# hp45BR.net
KiCad netlist of a schematic drawn in Altium Designer
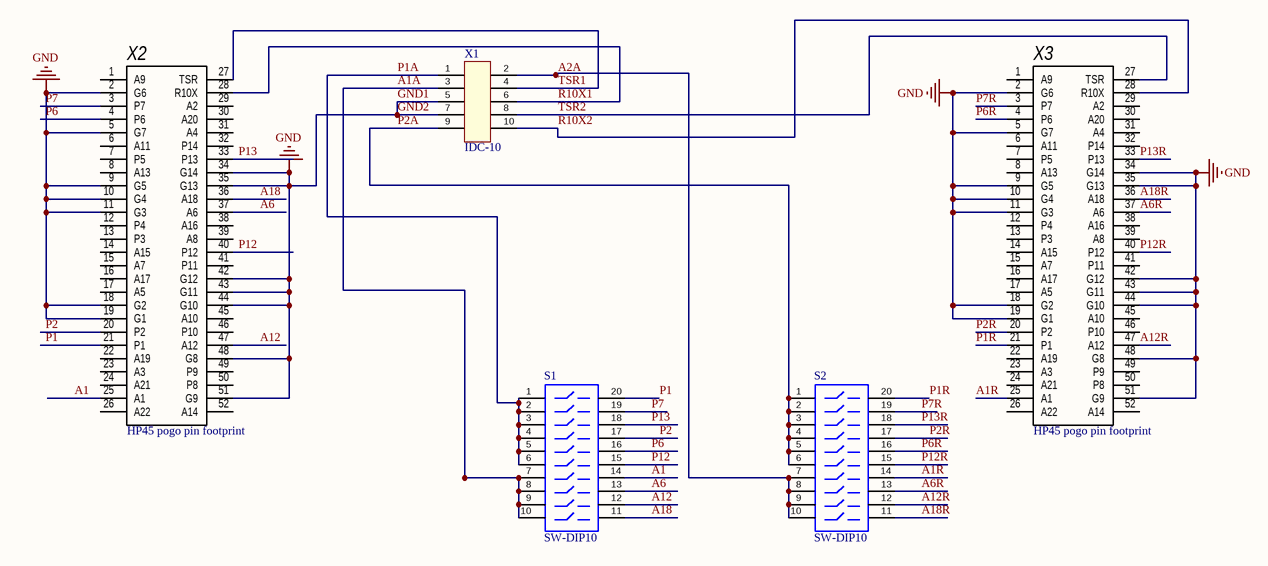
[diagram p0: hp45BR.SchDoc]

(export (version "E")
  (design (tool "Eeschema 10.0.6"))
  (components
    (comp (ref "S1")
      (value "SW-DIP10")
      (footprint "DIP-20-KEY")
      (description "4009 Series DIP Switch, Raised actuator")
      (fields (field (name "PUBLISHER") "Altium Limited"))
      (libsource (lib "RCU") (part "SW-DIP10"))
    )
    (comp (ref "S2")
      (value "SW-DIP10")
      (footprint "DIP-20-KEY")
      (description "4009 Series DIP Switch, Raised actuator")
      (fields (field (name "PUBLISHER") "Altium Limited"))
      (libsource (lib "RCU") (part "SW-DIP10"))
    )
    (comp (ref "X1")
      (value "IDC-10")
      (footprint "IDC-10")
      (description "разъем 4130")
      (libsource (lib "RCU") (part "IDC-10"))
    )
    (comp (ref "X2")
      (value "HP45 pogo pin footprint")
      (footprint "HP45")
      (libsource (lib "HP45") (part "HP45"))
    )
    (comp (ref "X3")
      (value "HP45 pogo pin footprint")
      (footprint "HP45")
      (libsource (lib "HP45") (part "HP45"))
    )
  )
  (nets
    (net (code "1") (name "/A1") (class "Default")
      (node (ref "S1") (pin "14") (pinfunction "14_14") (pintype "passive"))
      (node (ref "X2") (pin "25") (pinfunction "A1_25") (pintype "passive"))
    )
    (net (code "2") (name "/A1A") (class "Default")
      (node (ref "S1") (pin "10") (pinfunction "10_10") (pintype "passive"))
      (node (ref "S1") (pin "7") (pinfunction "7_7") (pintype "passive"))
      (node (ref "S1") (pin "8") (pinfunction "8_8") (pintype "passive"))
      (node (ref "S1") (pin "9") (pinfunction "9_9") (pintype "passive"))
      (node (ref "X1") (pin "3") (pinfunction "3_3") (pintype "passive"))
    )
    (net (code "3") (name "/A1R") (class "Default")
      (node (ref "S2") (pin "14") (pinfunction "14_14") (pintype "passive"))
      (node (ref "X3") (pin "25") (pinfunction "A1_25") (pintype "passive"))
    )
    (net (code "4") (name "/A2A") (class "Default")
      (node (ref "S2") (pin "10") (pinfunction "10_10") (pintype "passive"))
      (node (ref "S2") (pin "7") (pinfunction "7_7") (pintype "passive"))
      (node (ref "S2") (pin "8") (pinfunction "8_8") (pintype "passive"))
      (node (ref "S2") (pin "9") (pinfunction "9_9") (pintype "passive"))
      (node (ref "X1") (pin "2") (pinfunction "2_2") (pintype "passive"))
    )
    (net (code "5") (name "/A6") (class "Default")
      (node (ref "S1") (pin "13") (pinfunction "13_13") (pintype "passive"))
      (node (ref "X2") (pin "37") (pinfunction "A6_37") (pintype "passive"))
    )
    (net (code "6") (name "/A6R") (class "Default")
      (node (ref "S2") (pin "13") (pinfunction "13_13") (pintype "passive"))
      (node (ref "X3") (pin "37") (pinfunction "A6_37") (pintype "passive"))
    )
    (net (code "7") (name "/A12") (class "Default")
      (node (ref "S1") (pin "12") (pinfunction "12_12") (pintype "passive"))
      (node (ref "X2") (pin "47") (pinfunction "A12_47") (pintype "passive"))
    )
    (net (code "8") (name "/A12R") (class "Default")
      (node (ref "S2") (pin "12") (pinfunction "12_12") (pintype "passive"))
      (node (ref "X3") (pin "47") (pinfunction "A12_47") (pintype "passive"))
    )
    (net (code "9") (name "/A18") (class "Default")
      (node (ref "S1") (pin "11") (pinfunction "11_11") (pintype "passive"))
      (node (ref "X2") (pin "36") (pinfunction "A18_36") (pintype "passive"))
    )
    (net (code "10") (name "/A18R") (class "Default")
      (node (ref "S2") (pin "11") (pinfunction "11_11") (pintype "passive"))
      (node (ref "X3") (pin "36") (pinfunction "A18_36") (pintype "passive"))
    )
    (net (code "11") (name "/P1") (class "Default")
      (node (ref "S1") (pin "20") (pinfunction "20_20") (pintype "passive"))
      (node (ref "X2") (pin "21") (pinfunction "P1_21") (pintype "passive"))
    )
    (net (code "12") (name "/P1A") (class "Default")
      (node (ref "S1") (pin "1") (pinfunction "1_1") (pintype "passive"))
      (node (ref "S1") (pin "2") (pinfunction "2_2") (pintype "passive"))
      (node (ref "S1") (pin "3") (pinfunction "3_3") (pintype "passive"))
      (node (ref "S1") (pin "4") (pinfunction "4_4") (pintype "passive"))
      (node (ref "S1") (pin "5") (pinfunction "5_5") (pintype "passive"))
      (node (ref "S1") (pin "6") (pinfunction "6_6") (pintype "passive"))
      (node (ref "X1") (pin "1") (pinfunction "1_1") (pintype "passive"))
    )
    (net (code "13") (name "/P1R") (class "Default")
      (node (ref "S2") (pin "20") (pinfunction "20_20") (pintype "passive"))
      (node (ref "X3") (pin "21") (pinfunction "P1_21") (pintype "passive"))
    )
    (net (code "14") (name "/P2") (class "Default")
      (node (ref "S1") (pin "17") (pinfunction "17_17") (pintype "passive"))
      (node (ref "X2") (pin "20") (pinfunction "P2_20") (pintype "passive"))
    )
    (net (code "15") (name "/P2A") (class "Default")
      (node (ref "S2") (pin "1") (pinfunction "1_1") (pintype "passive"))
      (node (ref "S2") (pin "2") (pinfunction "2_2") (pintype "passive"))
      (node (ref "S2") (pin "3") (pinfunction "3_3") (pintype "passive"))
      (node (ref "S2") (pin "4") (pinfunction "4_4") (pintype "passive"))
      (node (ref "S2") (pin "5") (pinfunction "5_5") (pintype "passive"))
      (node (ref "S2") (pin "6") (pinfunction "6_6") (pintype "passive"))
      (node (ref "X1") (pin "9") (pinfunction "9_9") (pintype "passive"))
    )
    (net (code "16") (name "/P2R") (class "Default")
      (node (ref "S2") (pin "17") (pinfunction "17_17") (pintype "passive"))
      (node (ref "X3") (pin "20") (pinfunction "P2_20") (pintype "passive"))
    )
    (net (code "17") (name "/P6") (class "Default")
      (node (ref "S1") (pin "16") (pinfunction "16_16") (pintype "passive"))
      (node (ref "X2") (pin "4") (pinfunction "P6_4") (pintype "passive"))
    )
    (net (code "18") (name "/P6R") (class "Default")
      (node (ref "S2") (pin "16") (pinfunction "16_16") (pintype "passive"))
      (node (ref "X3") (pin "4") (pinfunction "P6_4") (pintype "passive"))
    )
    (net (code "19") (name "/P7") (class "Default")
      (node (ref "S1") (pin "19") (pinfunction "19_19") (pintype "passive"))
      (node (ref "X2") (pin "3") (pinfunction "P7_3") (pintype "passive"))
    )
    (net (code "20") (name "/P7R") (class "Default")
      (node (ref "S2") (pin "19") (pinfunction "19_19") (pintype "passive"))
      (node (ref "X3") (pin "3") (pinfunction "P7_3") (pintype "passive"))
    )
    (net (code "21") (name "/P12") (class "Default")
      (node (ref "S1") (pin "15") (pinfunction "15_15") (pintype "passive"))
      (node (ref "X2") (pin "40") (pinfunction "P12_40") (pintype "passive"))
    )
    (net (code "22") (name "/P12R") (class "Default")
      (node (ref "S2") (pin "15") (pinfunction "15_15") (pintype "passive"))
      (node (ref "X3") (pin "40") (pinfunction "P12_40") (pintype "passive"))
    )
    (net (code "23") (name "/P13") (class "Default")
      (node (ref "S1") (pin "18") (pinfunction "18_18") (pintype "passive"))
      (node (ref "X2") (pin "33") (pinfunction "P13_33") (pintype "passive"))
    )
    (net (code "24") (name "/P13R") (class "Default")
      (node (ref "S2") (pin "18") (pinfunction "18_18") (pintype "passive"))
      (node (ref "X3") (pin "33") (pinfunction "P13_33") (pintype "passive"))
    )
    (net (code "25") (name "/R10X1") (class "Default")
      (node (ref "X1") (pin "6") (pinfunction "6_6") (pintype "passive"))
      (node (ref "X2") (pin "28") (pinfunction "R10X_28") (pintype "passive"))
    )
    (net (code "26") (name "/R10X2") (class "Default")
      (node (ref "X1") (pin "10") (pinfunction "10_10") (pintype "passive"))
      (node (ref "X3") (pin "28") (pinfunction "R10X_28") (pintype "passive"))
    )
    (net (code "27") (name "/TSR1") (class "Default")
      (node (ref "X1") (pin "4") (pinfunction "4_4") (pintype "passive"))
      (node (ref "X2") (pin "27") (pinfunction "TSR_27") (pintype "passive"))
    )
    (net (code "28") (name "/TSR2") (class "Default")
      (node (ref "X1") (pin "8") (pinfunction "8_8") (pintype "passive"))
      (node (ref "X3") (pin "27") (pinfunction "TSR_27") (pintype "passive"))
    )
    (net (code "29") (name "GND") (class "Default")
      (node (ref "X1") (pin "5") (pinfunction "5_5") (pintype "passive"))
      (node (ref "X1") (pin "7") (pinfunction "7_7") (pintype "passive"))
      (node (ref "X2") (pin "10") (pinfunction "G4_10") (pintype "passive"))
      (node (ref "X2") (pin "11") (pinfunction "G3_11") (pintype "passive"))
      (node (ref "X2") (pin "18") (pinfunction "G2_18") (pintype "passive"))
      (node (ref "X2") (pin "19") (pinfunction "G1_19") (pintype "passive"))
      (node (ref "X2") (pin "2") (pinfunction "G6_2") (pintype "passive"))
      (node (ref "X2") (pin "34") (pinfunction "G14_34") (pintype "passive"))
      (node (ref "X2") (pin "35") (pinfunction "G13_35") (pintype "passive"))
      (node (ref "X2") (pin "42") (pinfunction "G12_42") (pintype "passive"))
      (node (ref "X2") (pin "43") (pinfunction "G11_43") (pintype "passive"))
      (node (ref "X2") (pin "44") (pinfunction "G10_44") (pintype "passive"))
      (node (ref "X2") (pin "48") (pinfunction "G8_48") (pintype "passive"))
      (node (ref "X2") (pin "5") (pinfunction "G7_5") (pintype "passive"))
      (node (ref "X2") (pin "51") (pinfunction "G9_51") (pintype "passive"))
      (node (ref "X2") (pin "9") (pinfunction "G5_9") (pintype "passive"))
      (node (ref "X3") (pin "10") (pinfunction "G4_10") (pintype "passive"))
      (node (ref "X3") (pin "11") (pinfunction "G3_11") (pintype "passive"))
      (node (ref "X3") (pin "18") (pinfunction "G2_18") (pintype "passive"))
      (node (ref "X3") (pin "19") (pinfunction "G1_19") (pintype "passive"))
      (node (ref "X3") (pin "2") (pinfunction "G6_2") (pintype "passive"))
      (node (ref "X3") (pin "34") (pinfunction "G14_34") (pintype "passive"))
      (node (ref "X3") (pin "35") (pinfunction "G13_35") (pintype "passive"))
      (node (ref "X3") (pin "42") (pinfunction "G12_42") (pintype "passive"))
      (node (ref "X3") (pin "43") (pinfunction "G11_43") (pintype "passive"))
      (node (ref "X3") (pin "44") (pinfunction "G10_44") (pintype "passive"))
      (node (ref "X3") (pin "48") (pinfunction "G8_48") (pintype "passive"))
      (node (ref "X3") (pin "5") (pinfunction "G7_5") (pintype "passive"))
      (node (ref "X3") (pin "51") (pinfunction "G9_51") (pintype "passive"))
      (node (ref "X3") (pin "9") (pinfunction "G5_9") (pintype "passive"))
    )
    (net (code "30") (name "unconnected-(X2-A2-Pad29)") (class "Default")
      (node (ref "X2") (pin "29") (pinfunction "A2_29") (pintype "passive"))
    )
    (net (code "31") (name "unconnected-(X2-A3-Pad23)") (class "Default")
      (node (ref "X2") (pin "23") (pinfunction "A3_23") (pintype "passive"))
    )
    (net (code "32") (name "unconnected-(X2-A4-Pad31)") (class "Default")
      (node (ref "X2") (pin "31") (pinfunction "A4_31") (pintype "passive"))
    )
    (net (code "33") (name "unconnected-(X2-A5-Pad17)") (class "Default")
      (node (ref "X2") (pin "17") (pinfunction "A5_17") (pintype "passive"))
    )
    (net (code "34") (name "unconnected-(X2-A7-Pad15)") (class "Default")
      (node (ref "X2") (pin "15") (pinfunction "A7_15") (pintype "passive"))
    )
    (net (code "35") (name "unconnected-(X2-A8-Pad39)") (class "Default")
      (node (ref "X2") (pin "39") (pinfunction "A8_39") (pintype "passive"))
    )
    (net (code "36") (name "unconnected-(X2-A9-Pad1)") (class "Default")
      (node (ref "X2") (pin "1") (pinfunction "A9_1") (pintype "passive"))
    )
    (net (code "37") (name "unconnected-(X2-A10-Pad45)") (class "Default")
      (node (ref "X2") (pin "45") (pinfunction "A10_45") (pintype "passive"))
    )
    (net (code "38") (name "unconnected-(X2-A11-Pad6)") (class "Default")
      (node (ref "X2") (pin "6") (pinfunction "A11_6") (pintype "passive"))
    )
    (net (code "39") (name "unconnected-(X2-A13-Pad8)") (class "Default")
      (node (ref "X2") (pin "8") (pinfunction "A13_8") (pintype "passive"))
    )
    (net (code "40") (name "unconnected-(X2-A14-Pad52)") (class "Default")
      (node (ref "X2") (pin "52") (pinfunction "A14_52") (pintype "passive"))
    )
    (net (code "41") (name "unconnected-(X2-A15-Pad14)") (class "Default")
      (node (ref "X2") (pin "14") (pinfunction "A15_14") (pintype "passive"))
    )
    (net (code "42") (name "unconnected-(X2-A16-Pad38)") (class "Default")
      (node (ref "X2") (pin "38") (pinfunction "A16_38") (pintype "passive"))
    )
    (net (code "43") (name "unconnected-(X2-A17-Pad16)") (class "Default")
      (node (ref "X2") (pin "16") (pinfunction "A17_16") (pintype "passive"))
    )
    (net (code "44") (name "unconnected-(X2-A19-Pad22)") (class "Default")
      (node (ref "X2") (pin "22") (pinfunction "A19_22") (pintype "passive"))
    )
    (net (code "45") (name "unconnected-(X2-A20-Pad30)") (class "Default")
      (node (ref "X2") (pin "30") (pinfunction "A20_30") (pintype "passive"))
    )
    (net (code "46") (name "unconnected-(X2-A21-Pad24)") (class "Default")
      (node (ref "X2") (pin "24") (pinfunction "A21_24") (pintype "passive"))
    )
    (net (code "47") (name "unconnected-(X2-A22-Pad26)") (class "Default")
      (node (ref "X2") (pin "26") (pinfunction "A22_26") (pintype "passive"))
    )
    (net (code "48") (name "unconnected-(X2-P3-Pad13)") (class "Default")
      (node (ref "X2") (pin "13") (pinfunction "P3_13") (pintype "passive"))
    )
    (net (code "49") (name "unconnected-(X2-P4-Pad12)") (class "Default")
      (node (ref "X2") (pin "12") (pinfunction "P4_12") (pintype "passive"))
    )
    (net (code "50") (name "unconnected-(X2-P5-Pad7)") (class "Default")
      (node (ref "X2") (pin "7") (pinfunction "P5_7") (pintype "passive"))
    )
    (net (code "51") (name "unconnected-(X2-P8-Pad50)") (class "Default")
      (node (ref "X2") (pin "50") (pinfunction "P8_50") (pintype "passive"))
    )
    (net (code "52") (name "unconnected-(X2-P9-Pad49)") (class "Default")
      (node (ref "X2") (pin "49") (pinfunction "P9_49") (pintype "passive"))
    )
    (net (code "53") (name "unconnected-(X2-P10-Pad46)") (class "Default")
      (node (ref "X2") (pin "46") (pinfunction "P10_46") (pintype "passive"))
    )
    (net (code "54") (name "unconnected-(X2-P11-Pad41)") (class "Default")
      (node (ref "X2") (pin "41") (pinfunction "P11_41") (pintype "passive"))
    )
    (net (code "55") (name "unconnected-(X2-P14-Pad32)") (class "Default")
      (node (ref "X2") (pin "32") (pinfunction "P14_32") (pintype "passive"))
    )
    (net (code "56") (name "unconnected-(X3-A2-Pad29)") (class "Default")
      (node (ref "X3") (pin "29") (pinfunction "A2_29") (pintype "passive"))
    )
    (net (code "57") (name "unconnected-(X3-A3-Pad23)") (class "Default")
      (node (ref "X3") (pin "23") (pinfunction "A3_23") (pintype "passive"))
    )
    (net (code "58") (name "unconnected-(X3-A4-Pad31)") (class "Default")
      (node (ref "X3") (pin "31") (pinfunction "A4_31") (pintype "passive"))
    )
    (net (code "59") (name "unconnected-(X3-A5-Pad17)") (class "Default")
      (node (ref "X3") (pin "17") (pinfunction "A5_17") (pintype "passive"))
    )
    (net (code "60") (name "unconnected-(X3-A7-Pad15)") (class "Default")
      (node (ref "X3") (pin "15") (pinfunction "A7_15") (pintype "passive"))
    )
    (net (code "61") (name "unconnected-(X3-A8-Pad39)") (class "Default")
      (node (ref "X3") (pin "39") (pinfunction "A8_39") (pintype "passive"))
    )
    (net (code "62") (name "unconnected-(X3-A9-Pad1)") (class "Default")
      (node (ref "X3") (pin "1") (pinfunction "A9_1") (pintype "passive"))
    )
    (net (code "63") (name "unconnected-(X3-A10-Pad45)") (class "Default")
      (node (ref "X3") (pin "45") (pinfunction "A10_45") (pintype "passive"))
    )
    (net (code "64") (name "unconnected-(X3-A11-Pad6)") (class "Default")
      (node (ref "X3") (pin "6") (pinfunction "A11_6") (pintype "passive"))
    )
    (net (code "65") (name "unconnected-(X3-A13-Pad8)") (class "Default")
      (node (ref "X3") (pin "8") (pinfunction "A13_8") (pintype "passive"))
    )
    (net (code "66") (name "unconnected-(X3-A14-Pad52)") (class "Default")
      (node (ref "X3") (pin "52") (pinfunction "A14_52") (pintype "passive"))
    )
    (net (code "67") (name "unconnected-(X3-A15-Pad14)") (class "Default")
      (node (ref "X3") (pin "14") (pinfunction "A15_14") (pintype "passive"))
    )
    (net (code "68") (name "unconnected-(X3-A16-Pad38)") (class "Default")
      (node (ref "X3") (pin "38") (pinfunction "A16_38") (pintype "passive"))
    )
    (net (code "69") (name "unconnected-(X3-A17-Pad16)") (class "Default")
      (node (ref "X3") (pin "16") (pinfunction "A17_16") (pintype "passive"))
    )
    (net (code "70") (name "unconnected-(X3-A19-Pad22)") (class "Default")
      (node (ref "X3") (pin "22") (pinfunction "A19_22") (pintype "passive"))
    )
    (net (code "71") (name "unconnected-(X3-A20-Pad30)") (class "Default")
      (node (ref "X3") (pin "30") (pinfunction "A20_30") (pintype "passive"))
    )
    (net (code "72") (name "unconnected-(X3-A21-Pad24)") (class "Default")
      (node (ref "X3") (pin "24") (pinfunction "A21_24") (pintype "passive"))
    )
    (net (code "73") (name "unconnected-(X3-A22-Pad26)") (class "Default")
      (node (ref "X3") (pin "26") (pinfunction "A22_26") (pintype "passive"))
    )
    (net (code "74") (name "unconnected-(X3-P3-Pad13)") (class "Default")
      (node (ref "X3") (pin "13") (pinfunction "P3_13") (pintype "passive"))
    )
    (net (code "75") (name "unconnected-(X3-P4-Pad12)") (class "Default")
      (node (ref "X3") (pin "12") (pinfunction "P4_12") (pintype "passive"))
    )
    (net (code "76") (name "unconnected-(X3-P5-Pad7)") (class "Default")
      (node (ref "X3") (pin "7") (pinfunction "P5_7") (pintype "passive"))
    )
    (net (code "77") (name "unconnected-(X3-P8-Pad50)") (class "Default")
      (node (ref "X3") (pin "50") (pinfunction "P8_50") (pintype "passive"))
    )
    (net (code "78") (name "unconnected-(X3-P9-Pad49)") (class "Default")
      (node (ref "X3") (pin "49") (pinfunction "P9_49") (pintype "passive"))
    )
    (net (code "79") (name "unconnected-(X3-P10-Pad46)") (class "Default")
      (node (ref "X3") (pin "46") (pinfunction "P10_46") (pintype "passive"))
    )
    (net (code "80") (name "unconnected-(X3-P11-Pad41)") (class "Default")
      (node (ref "X3") (pin "41") (pinfunction "P11_41") (pintype "passive"))
    )
    (net (code "81") (name "unconnected-(X3-P14-Pad32)") (class "Default")
      (node (ref "X3") (pin "32") (pinfunction "P14_32") (pintype "passive"))
    )
  )
)
